# 10-USB-Prog.net
KiCad netlist of a schematic drawn in Altium Designer
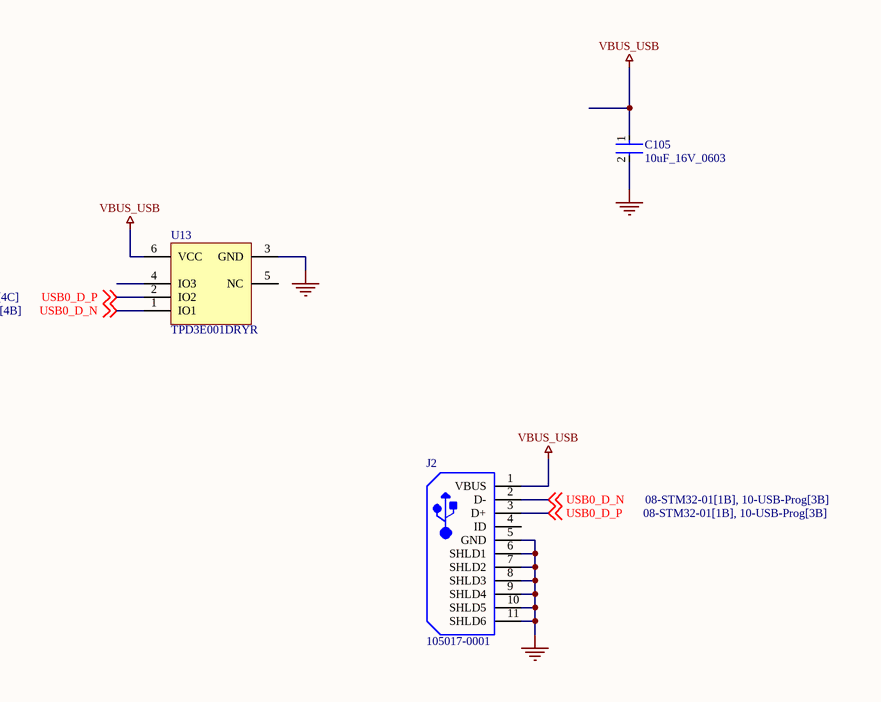
[diagram p0: 10-USB-Prog.SchDoc]

(export (version "E")
  (design (tool "Eeschema 10.0.6"))
  (components
    (comp (ref "C105")
      (value "10uF_16V_0603")
      (footprint "FP-0603-L_1_6_0_2-W_0_8_0-MFG")
      (description "Multilayer Ceramic Capacitor 10uF 16V X5R 20% SMD 0603 T/R")
      (fields (field (name "TOLERANCE") "20%"))
      (libsource (lib "Altium Content Vault") (part "b4654b650e69147ec39a6b967a45e02"))
    )
    (comp (ref "J2")
      (value "105017-0001")
      (footprint "USB-MICRO-B_V")
      (fields (field (name "MANUFACTURER") "Molex"))
      (libsource (lib "Altium Content Vault") (part "USB-5-6SHLD"))
    )
    (comp (ref "U13")
      (value "TPD3E001DRYR")
      (footprint "DRY0006A")
      (fields (field (name "MANUFACTURER") "Texas Instruments"))
      (libsource (lib "Altium Content Vault") (part "TI-TPD3E001-SON_DRY-6"))
    )
  )
  (nets
    (net (code "1") (name "GND") (class "Default")
      (node (ref "C105") (pin "2") (pinfunction "2_2") (pintype "passive"))
      (node (ref "J2") (pin "10") (pinfunction "SHLD5_10") (pintype "passive"))
      (node (ref "J2") (pin "11") (pinfunction "SHLD6_11") (pintype "passive"))
      (node (ref "J2") (pin "5") (pinfunction "GND_5") (pintype "passive"))
      (node (ref "J2") (pin "6") (pinfunction "SHLD1_6") (pintype "passive"))
      (node (ref "J2") (pin "7") (pinfunction "SHLD2_7") (pintype "passive"))
      (node (ref "J2") (pin "8") (pinfunction "SHLD3_8") (pintype "passive"))
      (node (ref "J2") (pin "9") (pinfunction "SHLD4_9") (pintype "passive"))
      (node (ref "U13") (pin "3") (pinfunction "GND_3") (pintype "power_in"))
    )
    (net (code "2") (name "USB0_D_N") (class "Default")
      (node (ref "J2") (pin "2") (pinfunction "D-_2") (pintype "passive"))
      (node (ref "U13") (pin "1") (pinfunction "IO1_1") (pintype "passive"))
    )
    (net (code "3") (name "USB0_D_P") (class "Default")
      (node (ref "J2") (pin "3") (pinfunction "D+_3") (pintype "passive"))
      (node (ref "U13") (pin "2") (pinfunction "IO2_2") (pintype "passive"))
    )
    (net (code "4") (name "VBUS_USB") (class "Default")
      (node (ref "C105") (pin "1") (pinfunction "1_1") (pintype "passive"))
      (node (ref "J2") (pin "1") (pinfunction "VBUS_1") (pintype "passive"))
      (node (ref "U13") (pin "6") (pinfunction "VCC_6") (pintype "power_in"))
    )
    (net (code "5") (name "unconnected-(J2-ID-Pad4)") (class "Default")
      (node (ref "J2") (pin "4") (pinfunction "ID_4") (pintype "passive"))
    )
    (net (code "6") (name "unconnected-(U13-IO3-Pad4)") (class "Default")
      (node (ref "U13") (pin "4") (pinfunction "IO3_4") (pintype "passive"))
    )
    (net (code "7") (name "unconnected-(U13-NC-Pad5)") (class "Default")
      (node (ref "U13") (pin "5") (pinfunction "NC_5") (pintype "passive"))
    )
  )
)
